# PressureModule.net
KiCad netlist of a schematic drawn in EAGLE
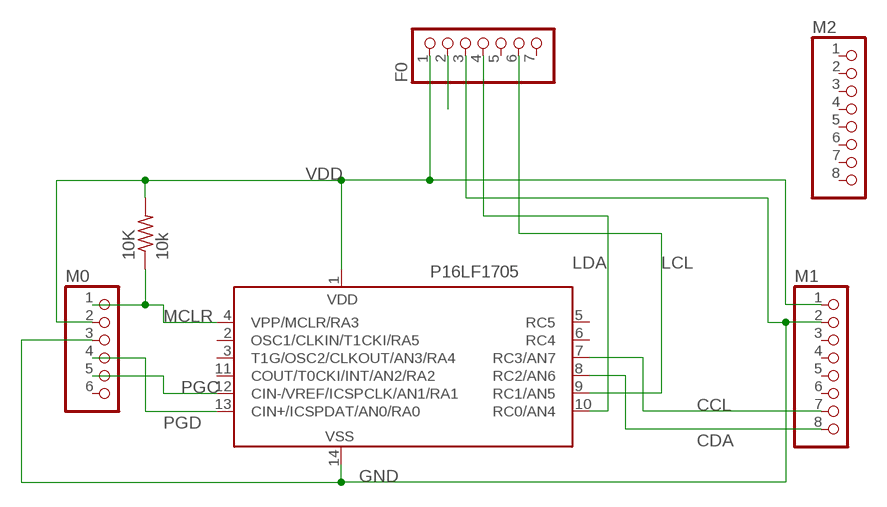
[diagram p0: schematic, sheet 1]

(export (version "E")
  (design (tool "Eeschema 10.0.6"))
  (components
    (comp (ref "10K")
      (value "10k")
      (footprint "eagle-import:0204_7")
      (libsource (lib "eagle-import") (part "R-US_0204/7"))
    )
    (comp (ref "F0")
      (value "PINHD-1X7")
      (footprint "eagle-import:1X07")
      (libsource (lib "eagle-import") (part "PINHD-1X7"))
    )
    (comp (ref "M0")
      (value "PINHD-1X6")
      (footprint "eagle-import:1X06")
      (libsource (lib "eagle-import") (part "PINHD-1X6"))
    )
    (comp (ref "M1")
      (value "PINHD-1X8")
      (footprint "eagle-import:1X08")
      (libsource (lib "eagle-import") (part "PINHD-1X8"))
    )
    (comp (ref "M2")
      (value "PINHD-1X8")
      (footprint "eagle-import:1X08")
      (libsource (lib "eagle-import") (part "PINHD-1X8"))
    )
    (comp (ref "P16LF1705")
      (value "PIC16F676SL")
      (footprint "eagle-import:SO-14")
      (fields (field (name "MF") "MICROCHIP") (field (name "MPN") "PIC16F676-I/SL"))
      (libsource (lib "eagle-import") (part "PIC16F676SL"))
    )
  )
  (nets
    (net (code "1") (name "/CCL") (class "Default")
      (node (ref "M1") (pin "7") (pinfunction "7_7") (pintype "passive"))
      (node (ref "P16LF1705") (pin "7") (pinfunction "RC3/AN7_7") (pintype "bidirectional"))
    )
    (net (code "2") (name "/CDA") (class "Default")
      (node (ref "M1") (pin "8") (pinfunction "8_8") (pintype "passive"))
      (node (ref "P16LF1705") (pin "8") (pinfunction "RC2/AN6_8") (pintype "bidirectional"))
    )
    (net (code "3") (name "/GND") (class "Default")
      (node (ref "F0") (pin "3") (pinfunction "3_3") (pintype "passive"))
      (node (ref "M0") (pin "3") (pinfunction "3_3") (pintype "passive"))
      (node (ref "M1") (pin "2") (pinfunction "2_2") (pintype "passive"))
      (node (ref "P16LF1705") (pin "14") (pinfunction "VSS_14") (pintype "power_in"))
    )
    (net (code "4") (name "/LCL") (class "Default")
      (node (ref "F0") (pin "6") (pinfunction "6_6") (pintype "passive"))
      (node (ref "P16LF1705") (pin "9") (pinfunction "RC1/AN5_9") (pintype "bidirectional"))
    )
    (net (code "5") (name "/LDA") (class "Default")
      (node (ref "F0") (pin "4") (pinfunction "4_4") (pintype "passive"))
      (node (ref "P16LF1705") (pin "10") (pinfunction "RC0/AN4_10") (pintype "bidirectional"))
    )
    (net (code "6") (name "/MCLR") (class "Default")
      (node (ref "10K") (pin "1") (pinfunction "1_1") (pintype "passive"))
      (node (ref "M0") (pin "1") (pinfunction "1_1") (pintype "passive"))
      (node (ref "P16LF1705") (pin "4") (pinfunction "VPP/MCLR/RA3_4") (pintype "input"))
    )
    (net (code "7") (name "/PGC") (class "Default")
      (node (ref "M0") (pin "5") (pinfunction "5_5") (pintype "passive"))
      (node (ref "P16LF1705") (pin "12") (pinfunction "CIN-/VREF/ICSPCLK/AN1/RA1_12") (pintype "bidirectional"))
    )
    (net (code "8") (name "/PGD") (class "Default")
      (node (ref "M0") (pin "4") (pinfunction "4_4") (pintype "passive"))
      (node (ref "P16LF1705") (pin "13") (pinfunction "CIN+/ICSPDAT/AN0/RA0_13") (pintype "bidirectional"))
    )
    (net (code "9") (name "/VDD") (class "Default")
      (node (ref "10K") (pin "2") (pinfunction "2_2") (pintype "passive"))
      (node (ref "F0") (pin "1") (pinfunction "1_1") (pintype "passive"))
      (node (ref "M0") (pin "2") (pinfunction "2_2") (pintype "passive"))
      (node (ref "M1") (pin "1") (pinfunction "1_1") (pintype "passive"))
      (node (ref "P16LF1705") (pin "1") (pinfunction "VDD_1") (pintype "power_in"))
    )
    (net (code "10") (name "unconnected-(F0-Pad2)") (class "Default")
      (node (ref "F0") (pin "2") (pinfunction "2_2") (pintype "passive"))
    )
    (net (code "11") (name "unconnected-(F0-Pad5)") (class "Default")
      (node (ref "F0") (pin "5") (pinfunction "5_5") (pintype "passive"))
    )
    (net (code "12") (name "unconnected-(F0-Pad7)") (class "Default")
      (node (ref "F0") (pin "7") (pinfunction "7_7") (pintype "passive"))
    )
    (net (code "13") (name "unconnected-(M0-Pad6)") (class "Default")
      (node (ref "M0") (pin "6") (pinfunction "6_6") (pintype "passive"))
    )
    (net (code "14") (name "unconnected-(M1-Pad3)") (class "Default")
      (node (ref "M1") (pin "3") (pinfunction "3_3") (pintype "passive"))
    )
    (net (code "15") (name "unconnected-(M1-Pad4)") (class "Default")
      (node (ref "M1") (pin "4") (pinfunction "4_4") (pintype "passive"))
    )
    (net (code "16") (name "unconnected-(M1-Pad5)") (class "Default")
      (node (ref "M1") (pin "5") (pinfunction "5_5") (pintype "passive"))
    )
    (net (code "17") (name "unconnected-(M1-Pad6)") (class "Default")
      (node (ref "M1") (pin "6") (pinfunction "6_6") (pintype "passive"))
    )
    (net (code "18") (name "unconnected-(M2-Pad1)") (class "Default")
      (node (ref "M2") (pin "1") (pinfunction "1_1") (pintype "passive"))
    )
    (net (code "19") (name "unconnected-(M2-Pad2)") (class "Default")
      (node (ref "M2") (pin "2") (pinfunction "2_2") (pintype "passive"))
    )
    (net (code "20") (name "unconnected-(M2-Pad3)") (class "Default")
      (node (ref "M2") (pin "3") (pinfunction "3_3") (pintype "passive"))
    )
    (net (code "21") (name "unconnected-(M2-Pad4)") (class "Default")
      (node (ref "M2") (pin "4") (pinfunction "4_4") (pintype "passive"))
    )
    (net (code "22") (name "unconnected-(M2-Pad5)") (class "Default")
      (node (ref "M2") (pin "5") (pinfunction "5_5") (pintype "passive"))
    )
    (net (code "23") (name "unconnected-(M2-Pad6)") (class "Default")
      (node (ref "M2") (pin "6") (pinfunction "6_6") (pintype "passive"))
    )
    (net (code "24") (name "unconnected-(M2-Pad7)") (class "Default")
      (node (ref "M2") (pin "7") (pinfunction "7_7") (pintype "passive"))
    )
    (net (code "25") (name "unconnected-(M2-Pad8)") (class "Default")
      (node (ref "M2") (pin "8") (pinfunction "8_8") (pintype "passive"))
    )
    (net (code "26") (name "unconnected-(P16LF1705-COUT{slash}T0CKI{slash}INT{slash}AN2{slash}RA2-Pad11)") (class "Default")
      (node (ref "P16LF1705") (pin "11") (pinfunction "COUT/T0CKI/INT/AN2/RA2_11") (pintype "bidirectional"))
    )
    (net (code "27") (name "unconnected-(P16LF1705-OSC1{slash}CLKIN{slash}T1CKI{slash}RA5-Pad2)") (class "Default")
      (node (ref "P16LF1705") (pin "2") (pinfunction "OSC1/CLKIN/T1CKI/RA5_2") (pintype "bidirectional"))
    )
    (net (code "28") (name "unconnected-(P16LF1705-RC4-Pad6)") (class "Default")
      (node (ref "P16LF1705") (pin "6") (pinfunction "RC4_6") (pintype "bidirectional"))
    )
    (net (code "29") (name "unconnected-(P16LF1705-RC5-Pad5)") (class "Default")
      (node (ref "P16LF1705") (pin "5") (pinfunction "RC5_5") (pintype "bidirectional"))
    )
    (net (code "30") (name "unconnected-(P16LF1705-T1G{slash}OSC2{slash}CLKOUT{slash}AN3{slash}RA4-Pad3)") (class "Default")
      (node (ref "P16LF1705") (pin "3") (pinfunction "T1G/OSC2/CLKOUT/AN3/RA4_3") (pintype "bidirectional"))
    )
  )
)
